# lpc_boilerplate.net
KiCad netlist of a schematic drawn in EAGLE
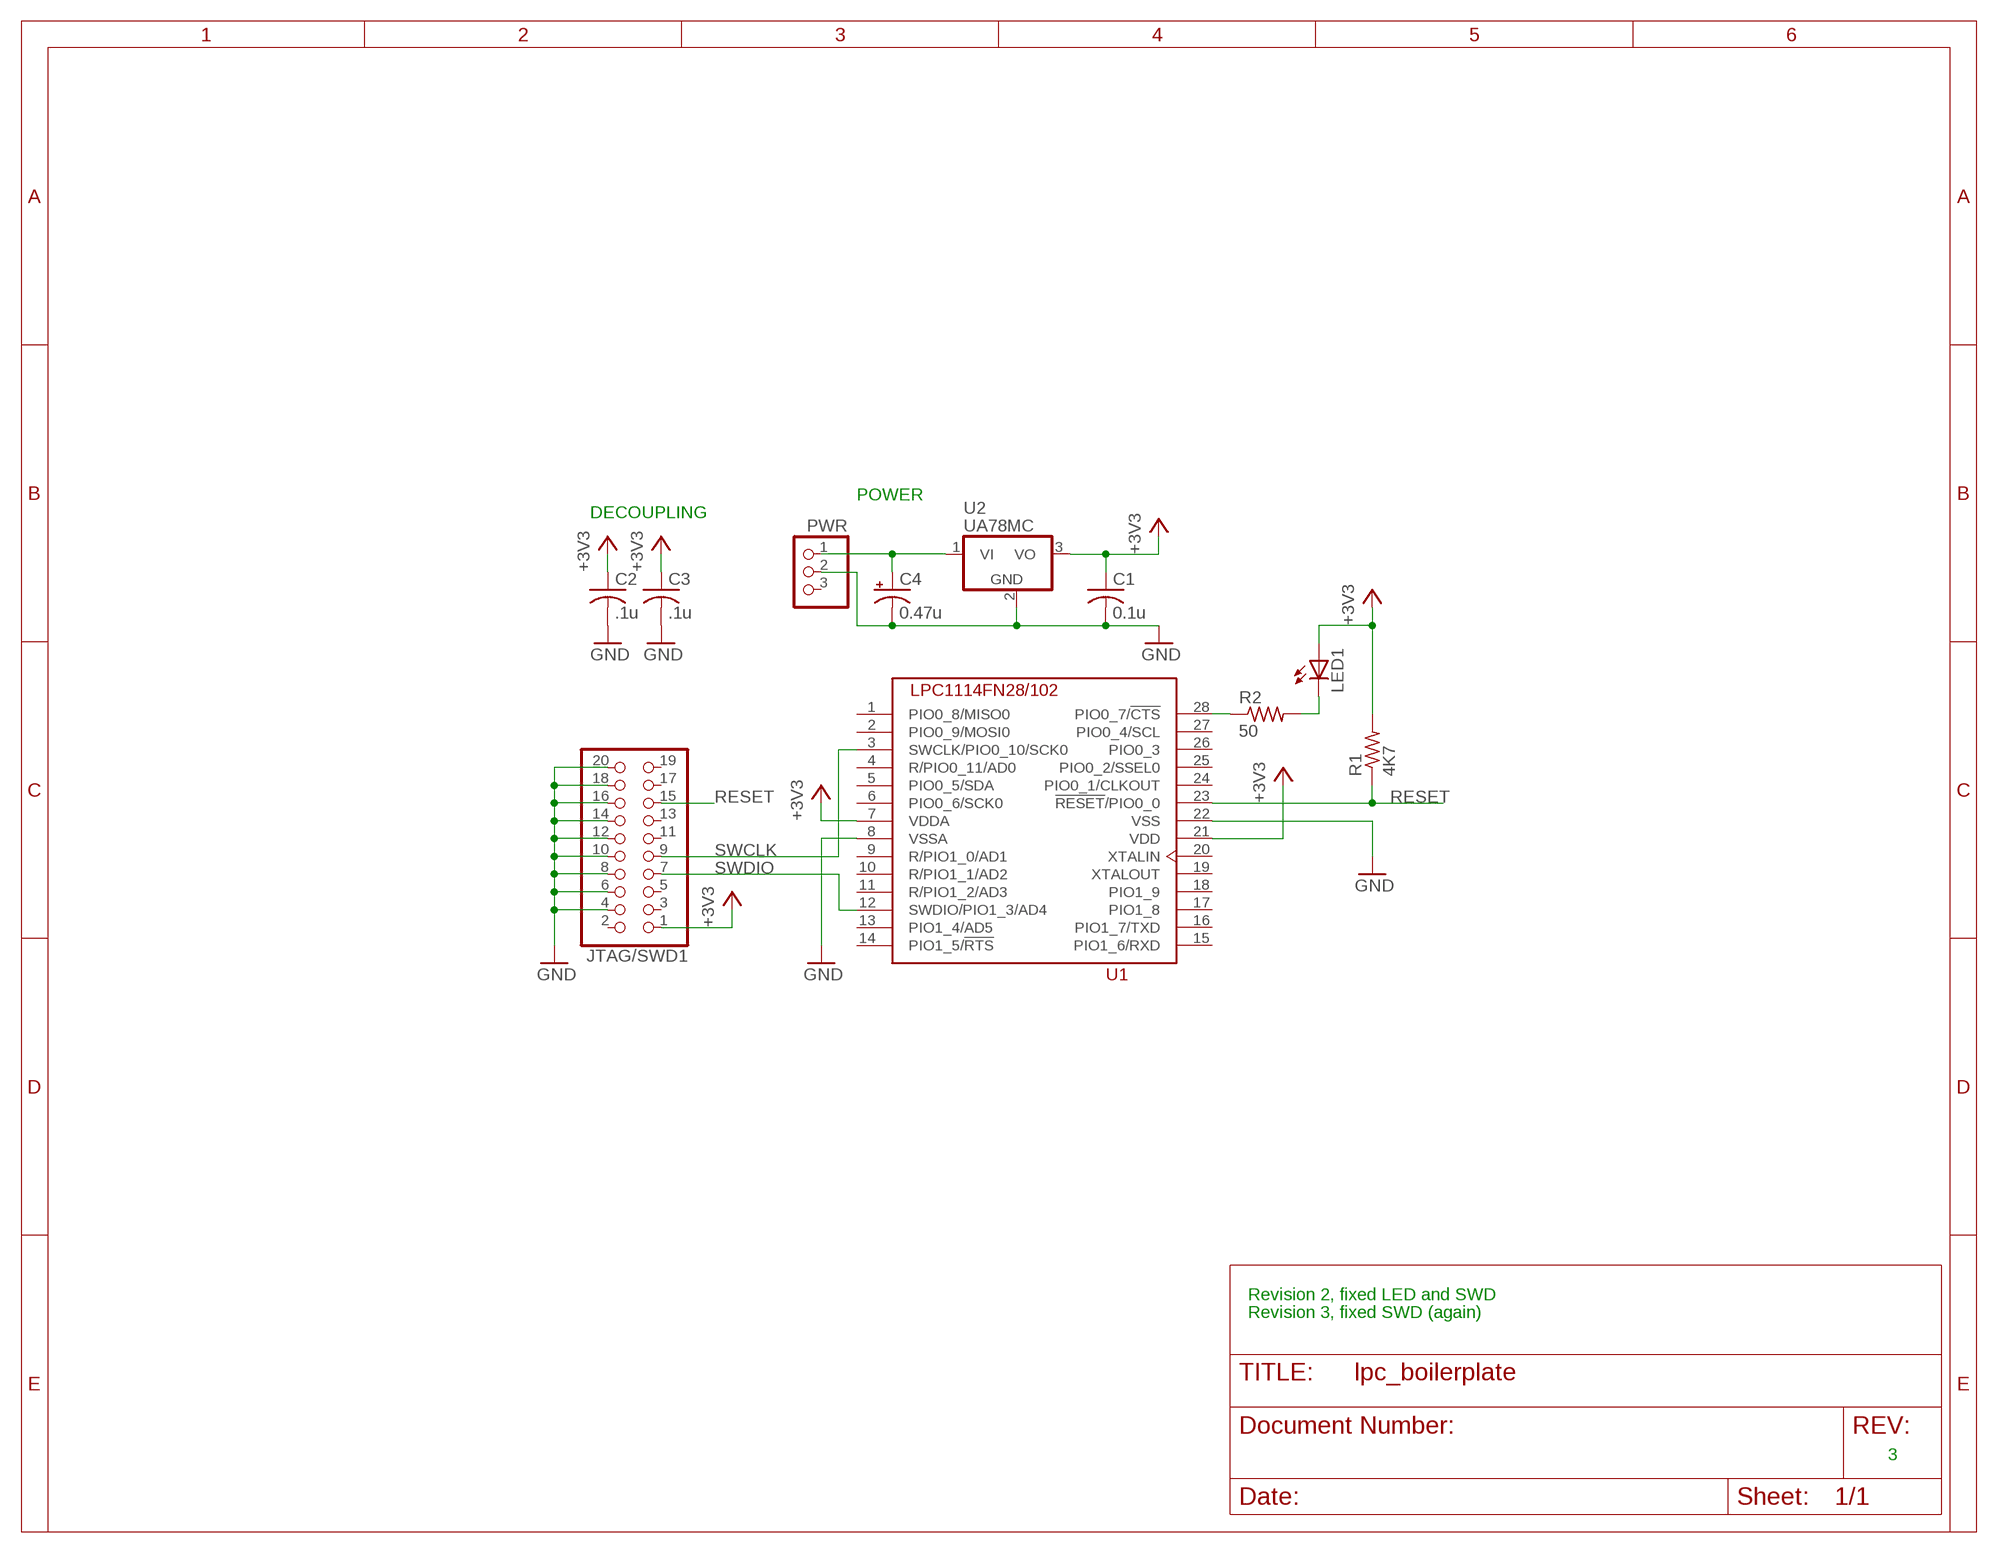
[diagram p0: schematic, sheet 1]

(export (version "E")
  (design (tool "Eeschema 10.0.6"))
  (components
    (comp (ref "C1")
      (value "0.1u")
      (footprint "eagle-import:C050-024X044")
      (libsource (lib "eagle-import") (part "C-US050-024X044"))
    )
    (comp (ref "C2")
      (value ".1u")
      (footprint "eagle-import:C050-024X044")
      (libsource (lib "eagle-import") (part "C-US050-024X044"))
    )
    (comp (ref "C3")
      (value ".1u")
      (footprint "eagle-import:C050-024X044")
      (libsource (lib "eagle-import") (part "C-US050-024X044"))
    )
    (comp (ref "C4")
      (value "0.47u")
      (footprint "eagle-import:E2-5")
      (libsource (lib "eagle-import") (part "CPOL-USE2-5"))
    )
    (comp (ref "JTAG/SWD1")
      (value "PINHD-2X10")
      (footprint "eagle-import:2X10")
      (libsource (lib "eagle-import") (part "PINHD-2X10"))
    )
    (comp (ref "LED1")
      (value "LED10MM")
      (footprint "eagle-import:LED10MM")
      (libsource (lib "eagle-import") (part "LED10MM"))
    )
    (comp (ref "PWR")
      (value "PINHD-1X3")
      (footprint "eagle-import:1X03")
      (libsource (lib "eagle-import") (part "PINHD-1X3"))
    )
    (comp (ref "R1")
      (value "4K7")
      (footprint "eagle-import:0207_10")
      (libsource (lib "eagle-import") (part "R-US_0207/10"))
    )
    (comp (ref "R2")
      (value "50")
      (footprint "eagle-import:0207_10")
      (libsource (lib "eagle-import") (part "R-US_0207/10"))
    )
    (comp (ref "U1")
      (value "LPC1114FN28/102")
      (footprint "eagle-import:DIL28-6")
      (libsource (lib "eagle-import") (part "LPC1114FN28/102"))
    )
    (comp (ref "U2")
      (value "UA78MC")
      (footprint "eagle-import:TO220V")
      (libsource (lib "eagle-import") (part "UA78MC"))
    )
  )
  (nets
    (net (code "1") (name "+3V3") (class "Default")
      (node (ref "C1") (pin "1") (pinfunction "1_1") (pintype "passive"))
      (node (ref "C2") (pin "1") (pinfunction "1_1") (pintype "passive"))
      (node (ref "C3") (pin "1") (pinfunction "1_1") (pintype "passive"))
      (node (ref "JTAG/SWD1") (pin "1") (pinfunction "1_1") (pintype "passive"))
      (node (ref "LED1") (pin "A") (pinfunction "A_A") (pintype "passive"))
      (node (ref "R1") (pin "2") (pinfunction "2_2") (pintype "passive"))
      (node (ref "U1") (pin "21") (pinfunction "VDD_21") (pintype "power_in"))
      (node (ref "U1") (pin "7") (pinfunction "VDDA_7") (pintype "power_in"))
      (node (ref "U2") (pin "3") (pinfunction "VO_3") (pintype "passive"))
    )
    (net (code "2") (name "/RESET") (class "Default")
      (node (ref "JTAG/SWD1") (pin "15") (pinfunction "15_15") (pintype "passive"))
      (node (ref "R1") (pin "1") (pinfunction "1_1") (pintype "passive"))
      (node (ref "U1") (pin "23") (pinfunction "~{RESET}/PIO0_0_23") (pintype "bidirectional"))
    )
    (net (code "3") (name "/SWCLK") (class "Default")
      (node (ref "JTAG/SWD1") (pin "9") (pinfunction "9_9") (pintype "passive"))
      (node (ref "U1") (pin "3") (pinfunction "SWCLK/PIO0_10/SCK0_3") (pintype "bidirectional"))
    )
    (net (code "4") (name "/SWDIO") (class "Default")
      (node (ref "JTAG/SWD1") (pin "7") (pinfunction "7_7") (pintype "passive"))
      (node (ref "U1") (pin "12") (pinfunction "SWDIO/PIO1_3/AD4_12") (pintype "bidirectional"))
    )
    (net (code "5") (name "GND") (class "Default")
      (node (ref "C1") (pin "2") (pinfunction "2_2") (pintype "passive"))
      (node (ref "C2") (pin "2") (pinfunction "2_2") (pintype "passive"))
      (node (ref "C3") (pin "2") (pinfunction "2_2") (pintype "passive"))
      (node (ref "C4") (pin "-") (pinfunction "-_-") (pintype "passive"))
      (node (ref "JTAG/SWD1") (pin "10") (pinfunction "10_10") (pintype "passive"))
      (node (ref "JTAG/SWD1") (pin "12") (pinfunction "12_12") (pintype "passive"))
      (node (ref "JTAG/SWD1") (pin "14") (pinfunction "14_14") (pintype "passive"))
      (node (ref "JTAG/SWD1") (pin "16") (pinfunction "16_16") (pintype "passive"))
      (node (ref "JTAG/SWD1") (pin "18") (pinfunction "18_18") (pintype "passive"))
      (node (ref "JTAG/SWD1") (pin "20") (pinfunction "20_20") (pintype "passive"))
      (node (ref "JTAG/SWD1") (pin "4") (pinfunction "4_4") (pintype "passive"))
      (node (ref "JTAG/SWD1") (pin "6") (pinfunction "6_6") (pintype "passive"))
      (node (ref "JTAG/SWD1") (pin "8") (pinfunction "8_8") (pintype "passive"))
      (node (ref "PWR") (pin "2") (pinfunction "2_2") (pintype "passive"))
      (node (ref "U1") (pin "22") (pinfunction "VSS_22") (pintype "power_in"))
      (node (ref "U1") (pin "8") (pinfunction "VSSA_8") (pintype "power_in"))
      (node (ref "U2") (pin "2") (pinfunction "GND_2") (pintype "passive"))
    )
    (net (code "6") (name "Net-(LED1-C)") (class "Default")
      (node (ref "LED1") (pin "K") (pinfunction "C_K") (pintype "passive"))
      (node (ref "R2") (pin "2") (pinfunction "2_2") (pintype "passive"))
    )
    (net (code "7") (name "Net-(U1-PIO0_7{slash}~{CTS})") (class "Default")
      (node (ref "R2") (pin "1") (pinfunction "1_1") (pintype "passive"))
      (node (ref "U1") (pin "28") (pinfunction "PIO0_7/~{CTS}_28") (pintype "bidirectional"))
    )
    (net (code "8") (name "Net-(U2-VI)") (class "Default")
      (node (ref "C4") (pin "+") (pinfunction "+_+") (pintype "passive"))
      (node (ref "PWR") (pin "1") (pinfunction "1_1") (pintype "passive"))
      (node (ref "U2") (pin "1") (pinfunction "VI_1") (pintype "input"))
    )
    (net (code "9") (name "unconnected-(JTAG/SWD1-Pad2)") (class "Default")
      (node (ref "JTAG/SWD1") (pin "2") (pinfunction "2_2") (pintype "passive"))
    )
    (net (code "10") (name "unconnected-(JTAG/SWD1-Pad3)") (class "Default")
      (node (ref "JTAG/SWD1") (pin "3") (pinfunction "3_3") (pintype "passive"))
    )
    (net (code "11") (name "unconnected-(JTAG/SWD1-Pad5)") (class "Default")
      (node (ref "JTAG/SWD1") (pin "5") (pinfunction "5_5") (pintype "passive"))
    )
    (net (code "12") (name "unconnected-(JTAG/SWD1-Pad11)") (class "Default")
      (node (ref "JTAG/SWD1") (pin "11") (pinfunction "11_11") (pintype "passive"))
    )
    (net (code "13") (name "unconnected-(JTAG/SWD1-Pad13)") (class "Default")
      (node (ref "JTAG/SWD1") (pin "13") (pinfunction "13_13") (pintype "passive"))
    )
    (net (code "14") (name "unconnected-(JTAG/SWD1-Pad17)") (class "Default")
      (node (ref "JTAG/SWD1") (pin "17") (pinfunction "17_17") (pintype "passive"))
    )
    (net (code "15") (name "unconnected-(JTAG/SWD1-Pad19)") (class "Default")
      (node (ref "JTAG/SWD1") (pin "19") (pinfunction "19_19") (pintype "passive"))
    )
    (net (code "16") (name "unconnected-(PWR-Pad3)") (class "Default")
      (node (ref "PWR") (pin "3") (pinfunction "3_3") (pintype "passive"))
    )
    (net (code "17") (name "unconnected-(U1-PIO0_1{slash}CLKOUT-Pad24)") (class "Default")
      (node (ref "U1") (pin "24") (pinfunction "PIO0_1/CLKOUT_24") (pintype "bidirectional"))
    )
    (net (code "18") (name "unconnected-(U1-PIO0_2{slash}SSEL0-Pad25)") (class "Default")
      (node (ref "U1") (pin "25") (pinfunction "PIO0_2/SSEL0_25") (pintype "bidirectional"))
    )
    (net (code "19") (name "unconnected-(U1-PIO0_3-Pad26)") (class "Default")
      (node (ref "U1") (pin "26") (pinfunction "PIO0_3_26") (pintype "bidirectional"))
    )
    (net (code "20") (name "unconnected-(U1-PIO0_4{slash}SCL-Pad27)") (class "Default")
      (node (ref "U1") (pin "27") (pinfunction "PIO0_4/SCL_27") (pintype "bidirectional"))
    )
    (net (code "21") (name "unconnected-(U1-PIO0_5{slash}SDA-Pad5)") (class "Default")
      (node (ref "U1") (pin "5") (pinfunction "PIO0_5/SDA_5") (pintype "bidirectional"))
    )
    (net (code "22") (name "unconnected-(U1-PIO0_6{slash}SCK0-Pad6)") (class "Default")
      (node (ref "U1") (pin "6") (pinfunction "PIO0_6/SCK0_6") (pintype "bidirectional"))
    )
    (net (code "23") (name "unconnected-(U1-PIO0_8{slash}MISO0-Pad1)") (class "Default")
      (node (ref "U1") (pin "1") (pinfunction "PIO0_8/MISO0_1") (pintype "bidirectional"))
    )
    (net (code "24") (name "unconnected-(U1-PIO0_9{slash}MOSI0-Pad2)") (class "Default")
      (node (ref "U1") (pin "2") (pinfunction "PIO0_9/MOSI0_2") (pintype "bidirectional"))
    )
    (net (code "25") (name "unconnected-(U1-PIO1_4{slash}AD5-Pad13)") (class "Default")
      (node (ref "U1") (pin "13") (pinfunction "PIO1_4/AD5_13") (pintype "bidirectional"))
    )
    (net (code "26") (name "unconnected-(U1-PIO1_5{slash}~{RTS}-Pad14)") (class "Default")
      (node (ref "U1") (pin "14") (pinfunction "PIO1_5/~{RTS}_14") (pintype "bidirectional"))
    )
    (net (code "27") (name "unconnected-(U1-PIO1_6{slash}RXD-Pad15)") (class "Default")
      (node (ref "U1") (pin "15") (pinfunction "PIO1_6/RXD_15") (pintype "bidirectional"))
    )
    (net (code "28") (name "unconnected-(U1-PIO1_7{slash}TXD-Pad16)") (class "Default")
      (node (ref "U1") (pin "16") (pinfunction "PIO1_7/TXD_16") (pintype "bidirectional"))
    )
    (net (code "29") (name "unconnected-(U1-PIO1_8-Pad17)") (class "Default")
      (node (ref "U1") (pin "17") (pinfunction "PIO1_8_17") (pintype "bidirectional"))
    )
    (net (code "30") (name "unconnected-(U1-PIO1_9-Pad18)") (class "Default")
      (node (ref "U1") (pin "18") (pinfunction "PIO1_9_18") (pintype "bidirectional"))
    )
    (net (code "31") (name "unconnected-(U1-R{slash}PIO0_11{slash}AD0-Pad4)") (class "Default")
      (node (ref "U1") (pin "4") (pinfunction "R/PIO0_11/AD0_4") (pintype "bidirectional"))
    )
    (net (code "32") (name "unconnected-(U1-R{slash}PIO1_0{slash}AD1-Pad9)") (class "Default")
      (node (ref "U1") (pin "9") (pinfunction "R/PIO1_0/AD1_9") (pintype "bidirectional"))
    )
    (net (code "33") (name "unconnected-(U1-R{slash}PIO1_1{slash}AD2-Pad10)") (class "Default")
      (node (ref "U1") (pin "10") (pinfunction "R/PIO1_1/AD2_10") (pintype "bidirectional"))
    )
    (net (code "34") (name "unconnected-(U1-R{slash}PIO1_2{slash}AD3-Pad11)") (class "Default")
      (node (ref "U1") (pin "11") (pinfunction "R/PIO1_2/AD3_11") (pintype "bidirectional"))
    )
    (net (code "35") (name "unconnected-(U1-XTALIN-Pad20)") (class "Default")
      (node (ref "U1") (pin "20") (pinfunction "XTALIN_20") (pintype "bidirectional"))
    )
    (net (code "36") (name "unconnected-(U1-XTALOUT-Pad19)") (class "Default")
      (node (ref "U1") (pin "19") (pinfunction "XTALOUT_19") (pintype "output"))
    )
  )
)
